# Current_measurement.net
KiCad netlist of a schematic drawn in Altium Designer
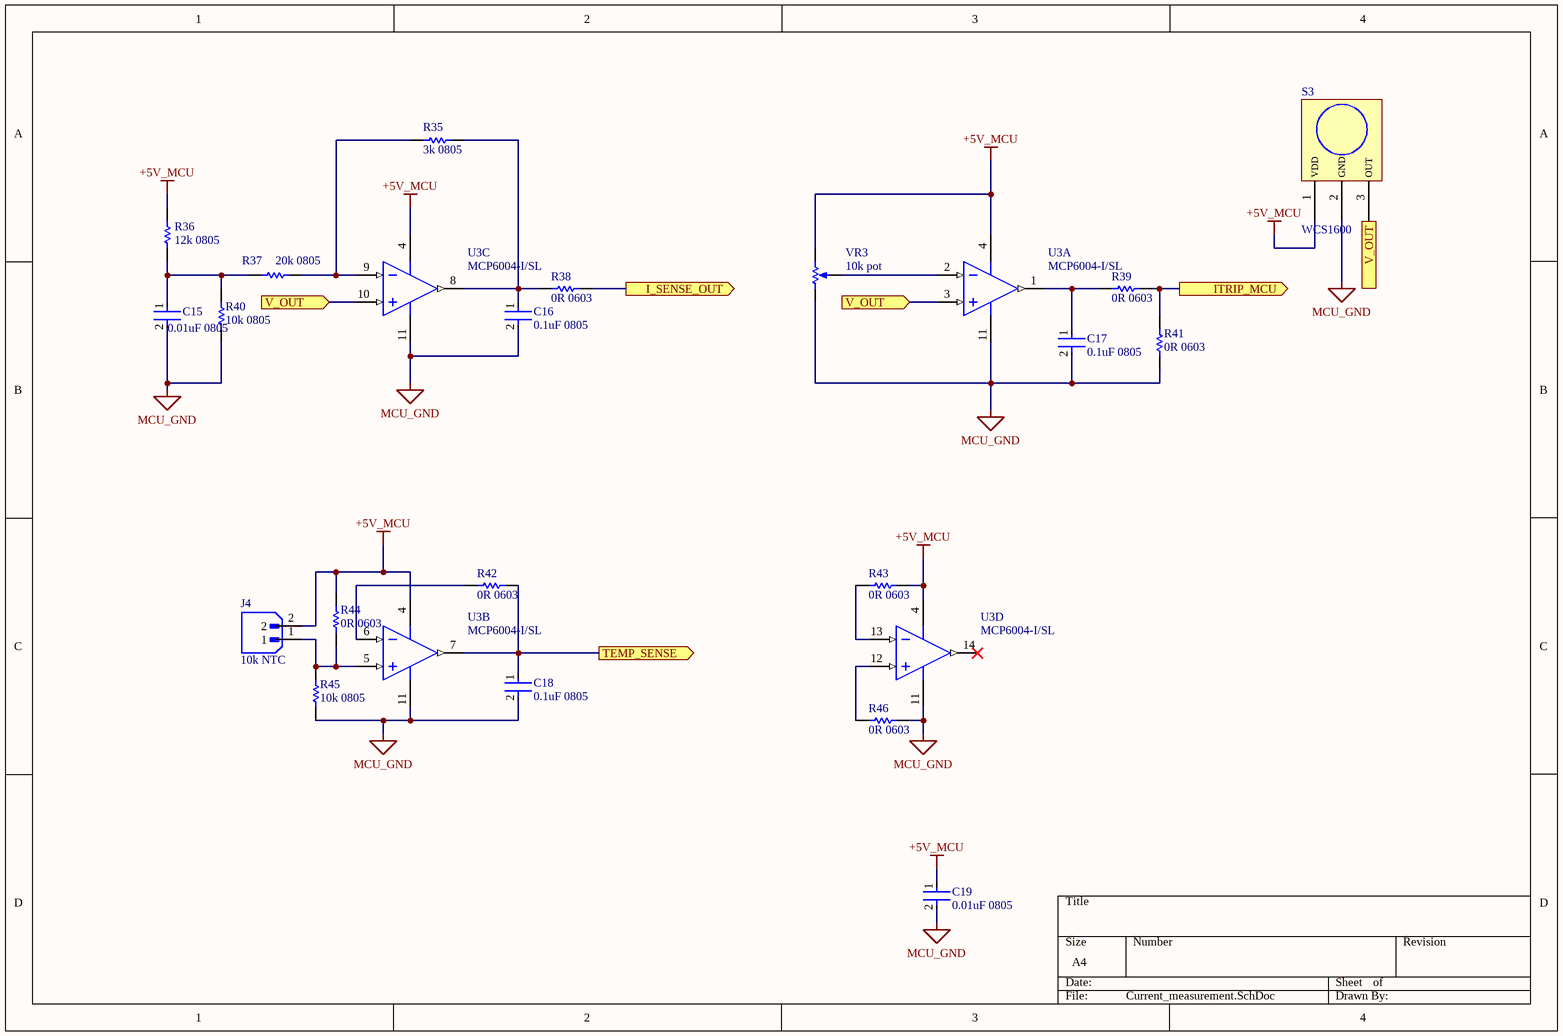
[diagram p0: Current_measurement.SchDoc]

(export (version "E")
  (design (tool "Eeschema 10.0.6"))
  (components
    (comp (ref "C15")
      (value "0.01uF 0805")
      (footprint "R0805")
      (description "10nF/0.01uF 50V Capacitor ±10% Tolerance 0805B103K500CT – 0805 Package")
      (libsource (lib "1kW_BLDC_Controller") (part "0.01uF 0805"))
    )
    (comp (ref "C16")
      (value "0.1uF 0805")
      (footprint "R0805")
      (description "0.1uF/100nF 100V Capacitor ±10% Tolerance CC0805KKX7R0BB104 – 0805 Package")
      (libsource (lib "1kW_BLDC_Controller") (part "0.1uF 0805"))
    )
    (comp (ref "C17")
      (value "0.1uF 0805")
      (footprint "R0805")
      (description "0.1uF/100nF 100V Capacitor ±10% Tolerance CC0805KKX7R0BB104 – 0805 Package")
      (libsource (lib "1kW_BLDC_Controller") (part "0.1uF 0805"))
    )
    (comp (ref "C18")
      (value "0.1uF 0805")
      (footprint "R0805")
      (description "0.1uF/100nF 100V Capacitor ±10% Tolerance CC0805KKX7R0BB104 – 0805 Package")
      (libsource (lib "1kW_BLDC_Controller") (part "0.1uF 0805"))
    )
    (comp (ref "C19")
      (value "0.01uF 0805")
      (footprint "R0805")
      (description "10nF/0.01uF 50V Capacitor ±10% Tolerance 0805B103K500CT – 0805 Package")
      (libsource (lib "1kW_BLDC_Controller") (part "0.01uF 0805"))
    )
    (comp (ref "J4")
      (value "10k NTC")
      (footprint "XH2.5-2p")
      (description "2 Pin JST-XH Male Straight 2515 Connector 2.54mm Pitch")
      (libsource (lib "1kW_BLDC_Controller_1") (part "XH2.5-2p"))
    )
    (comp (ref "R35")
      (value "3k 0805")
      (footprint "R0805")
      (description "3K Ohm 1/8 Watt Resistor 1% Tolerance 0805W8F3001T5E – 0805 Package")
      (libsource (lib "1kW_BLDC_Controller") (part "R0805"))
    )
    (comp (ref "R36")
      (value "12k 0805")
      (footprint "R0805")
      (description "12K Ohm 1/8 Watt Resistor 1% Tolerance RC0805FR-0712KL – 0805 Package")
      (libsource (lib "1kW_BLDC_Controller") (part "R0805"))
    )
    (comp (ref "R37")
      (value "20k 0805")
      (footprint "R0805")
      (description "20K ohm 1/8 Watt SMD Resistor 1% Tolerance RC0805FR-0720KL – 0805 Package")
      (libsource (lib "1kW_BLDC_Controller") (part "R0805"))
    )
    (comp (ref "R38")
      (value "0R 0603")
      (footprint "R0603")
      (description "0 Ohm 1/10 Watt Resistor 1% Tolerance RC0603FR-070RL – 0603 Package")
      (libsource (lib "1kW_BLDC_Controller") (part "R0000 0603"))
    )
    (comp (ref "R39")
      (value "0R 0603")
      (footprint "R0603")
      (description "0 Ohm 1/10 Watt Resistor 1% Tolerance RC0603FR-070RL – 0603 Package")
      (libsource (lib "1kW_BLDC_Controller") (part "R0000 0603"))
    )
    (comp (ref "R40")
      (value "10k 0805")
      (footprint "R0805")
      (description "10K Ohm 1/8 Watt Resistor 1% Tolerance RC0805FR-0710KL – 0805 Package")
      (libsource (lib "1kW_BLDC_Controller") (part "10k 0805"))
    )
    (comp (ref "R41")
      (value "0R 0603")
      (footprint "R0603")
      (description "0 Ohm 1/10 Watt Resistor 1% Tolerance RC0603FR-070RL – 0603 Package")
      (libsource (lib "1kW_BLDC_Controller") (part "R0000 0603"))
    )
    (comp (ref "R42")
      (value "0R 0603")
      (footprint "R0603")
      (description "0 Ohm 1/10 Watt Resistor 1% Tolerance RC0603FR-070RL – 0603 Package")
      (libsource (lib "1kW_BLDC_Controller") (part "R0000 0603"))
    )
    (comp (ref "R43")
      (value "0R 0603")
      (footprint "R0603")
      (description "0 Ohm 1/10 Watt Resistor 1% Tolerance RC0603FR-070RL – 0603 Package")
      (libsource (lib "1kW_BLDC_Controller") (part "R0000 0603"))
    )
    (comp (ref "R44")
      (value "0R 0603")
      (footprint "R0603")
      (description "0 Ohm 1/10 Watt Resistor 1% Tolerance RC0603FR-070RL – 0603 Package")
      (libsource (lib "1kW_BLDC_Controller") (part "R0000 0603"))
    )
    (comp (ref "R45")
      (value "10k 0805")
      (footprint "R0805")
      (description "10K Ohm 1/8 Watt Resistor 1% Tolerance RC0805FR-0710KL – 0805 Package")
      (libsource (lib "1kW_BLDC_Controller") (part "10k 0805"))
    )
    (comp (ref "R46")
      (value "0R 0603")
      (footprint "R0603")
      (description "0 Ohm 1/10 Watt Resistor 1% Tolerance RC0603FR-070RL – 0603 Package")
      (libsource (lib "1kW_BLDC_Controller") (part "R0000 0603"))
    )
    (comp (ref "S3")
      (value "WCS1600")
      (footprint "2.54mm 4p header")
      (description "WCS1600 100A Hall Effect Linear Current Sensor")
      (libsource (lib "1kW_BLDC_Controller") (part "WCS1600"))
    )
    (comp (ref "U3")
      (value "MCP6004-I/SL")
      (footprint "SOIC-SL14_M")
      (description "MCP6004 1MHz Rail-to-Rail Operational Amplifier – SOIC-14 Package")
      (libsource (lib "Altium Content Vault") (part "AMP-OPA-MCP6004-IL14"))
    )
    (comp (ref "VR3")
      (value "10k pot")
      (footprint "BOUR-3299W-3_V")
      (description "10K ohm Variable Resistor-Trimpot 3296 Package")
      (fields (field (name "TOLERANCE") "10%") (field (name "MANUFACTURER") "Bourns"))
      (libsource (lib "Altium Content Vault") (part "BOUR-3299X-3"))
    )
  )
  (nets
    (net (code "1") (name "+5V_MCU") (class "Default")
      (node (ref "C19") (pin "1") (pinfunction "1_1") (pintype "passive"))
      (node (ref "J4") (pin "2") (pinfunction "2_2") (pintype "passive"))
      (node (ref "R36") (pin "2") (pinfunction "2_2") (pintype "passive"))
      (node (ref "R43") (pin "2") (pinfunction "2_2") (pintype "passive"))
      (node (ref "R44") (pin "2") (pinfunction "2_2") (pintype "passive"))
      (node (ref "S3") (pin "1") (pinfunction "VDD_1") (pintype "power_in"))
      (node (ref "U3") (pin "4") (pinfunction "VDD_4") (pintype "power_in"))
      (node (ref "VR3") (pin "1") (pinfunction "CCW_1") (pintype "passive"))
    )
    (net (code "2") (name "/ITRIP_MCU") (class "Default")
      (node (ref "R39") (pin "2") (pinfunction "2_2") (pintype "passive"))
      (node (ref "R41") (pin "2") (pinfunction "2_2") (pintype "passive"))
    )
    (net (code "3") (name "/I_SENSE_OUT") (class "Default")
      (node (ref "R38") (pin "2") (pinfunction "2_2") (pintype "passive"))
    )
    (net (code "4") (name "/TEMP_SENSE") (class "Default")
      (node (ref "C18") (pin "1") (pinfunction "1_1") (pintype "passive"))
      (node (ref "R42") (pin "2") (pinfunction "2_2") (pintype "passive"))
      (node (ref "U3") (pin "7") (pinfunction "VOUTB_7") (pintype "output"))
    )
    (net (code "5") (name "/V_OUT") (class "Default")
      (node (ref "S3") (pin "3") (pinfunction "OUT_3") (pintype "passive"))
      (node (ref "U3") (pin "10") (pinfunction "VINC+_10") (pintype "input"))
      (node (ref "U3") (pin "3") (pinfunction "VINA+_3") (pintype "input"))
    )
    (net (code "6") (name "MCU_GND") (class "Default")
      (node (ref "C15") (pin "2") (pinfunction "2_2") (pintype "passive"))
      (node (ref "C16") (pin "2") (pinfunction "2_2") (pintype "passive"))
      (node (ref "C17") (pin "2") (pinfunction "2_2") (pintype "passive"))
      (node (ref "C18") (pin "2") (pinfunction "2_2") (pintype "passive"))
      (node (ref "C19") (pin "2") (pinfunction "2_2") (pintype "passive"))
      (node (ref "R40") (pin "1") (pinfunction "1_1") (pintype "passive"))
      (node (ref "R41") (pin "1") (pinfunction "1_1") (pintype "passive"))
      (node (ref "R45") (pin "1") (pinfunction "1_1") (pintype "passive"))
      (node (ref "R46") (pin "2") (pinfunction "2_2") (pintype "passive"))
      (node (ref "S3") (pin "2") (pinfunction "GND_2") (pintype "power_in"))
      (node (ref "U3") (pin "11") (pinfunction "VSS_11") (pintype "power_in"))
      (node (ref "VR3") (pin "3") (pinfunction "CW_3") (pintype "passive"))
    )
    (net (code "7") (name "Net-(C15-Pad1)") (class "Default")
      (node (ref "C15") (pin "1") (pinfunction "1_1") (pintype "passive"))
      (node (ref "R36") (pin "1") (pinfunction "1_1") (pintype "passive"))
      (node (ref "R37") (pin "1") (pinfunction "1_1") (pintype "passive"))
      (node (ref "R40") (pin "2") (pinfunction "2_2") (pintype "passive"))
    )
    (net (code "8") (name "Net-(U3A-VINA-)") (class "Default")
      (node (ref "U3") (pin "2") (pinfunction "VINA-_2") (pintype "input"))
      (node (ref "VR3") (pin "2") (pinfunction "WIPER_2") (pintype "passive"))
    )
    (net (code "9") (name "Net-(U3A-VOUTA)") (class "Default")
      (node (ref "C17") (pin "1") (pinfunction "1_1") (pintype "passive"))
      (node (ref "R39") (pin "1") (pinfunction "1_1") (pintype "passive"))
      (node (ref "U3") (pin "1") (pinfunction "VOUTA_1") (pintype "output"))
    )
    (net (code "10") (name "Net-(U3B-VINB+)") (class "Default")
      (node (ref "J4") (pin "1") (pinfunction "1_1") (pintype "passive"))
      (node (ref "R44") (pin "1") (pinfunction "1_1") (pintype "passive"))
      (node (ref "R45") (pin "2") (pinfunction "2_2") (pintype "passive"))
      (node (ref "U3") (pin "5") (pinfunction "VINB+_5") (pintype "input"))
    )
    (net (code "11") (name "Net-(U3B-VINB-)") (class "Default")
      (node (ref "R42") (pin "1") (pinfunction "1_1") (pintype "passive"))
      (node (ref "U3") (pin "6") (pinfunction "VINB-_6") (pintype "input"))
    )
    (net (code "12") (name "Net-(U3C-VINC-)") (class "Default")
      (node (ref "R35") (pin "1") (pinfunction "1_1") (pintype "passive"))
      (node (ref "R37") (pin "2") (pinfunction "2_2") (pintype "passive"))
      (node (ref "U3") (pin "9") (pinfunction "VINC-_9") (pintype "input"))
    )
    (net (code "13") (name "Net-(U3C-VOUTC)") (class "Default")
      (node (ref "C16") (pin "1") (pinfunction "1_1") (pintype "passive"))
      (node (ref "R35") (pin "2") (pinfunction "2_2") (pintype "passive"))
      (node (ref "R38") (pin "1") (pinfunction "1_1") (pintype "passive"))
      (node (ref "U3") (pin "8") (pinfunction "VOUTC_8") (pintype "output"))
    )
    (net (code "14") (name "Net-(U3D-VIND+)") (class "Default")
      (node (ref "R46") (pin "1") (pinfunction "1_1") (pintype "passive"))
      (node (ref "U3") (pin "12") (pinfunction "VIND+_12") (pintype "input"))
    )
    (net (code "15") (name "Net-(U3D-VIND-)") (class "Default")
      (node (ref "R43") (pin "1") (pinfunction "1_1") (pintype "passive"))
      (node (ref "U3") (pin "13") (pinfunction "VIND-_13") (pintype "input"))
    )
    (net (code "16") (name "unconnected-(U3D-VOUTD-Pad14)") (class "Default")
      (node (ref "U3") (pin "14") (pinfunction "VOUTD_14") (pintype "output+no_connect"))
    )
  )
)
